# 4-20.net
KiCad netlist of a schematic drawn in Altium Designer
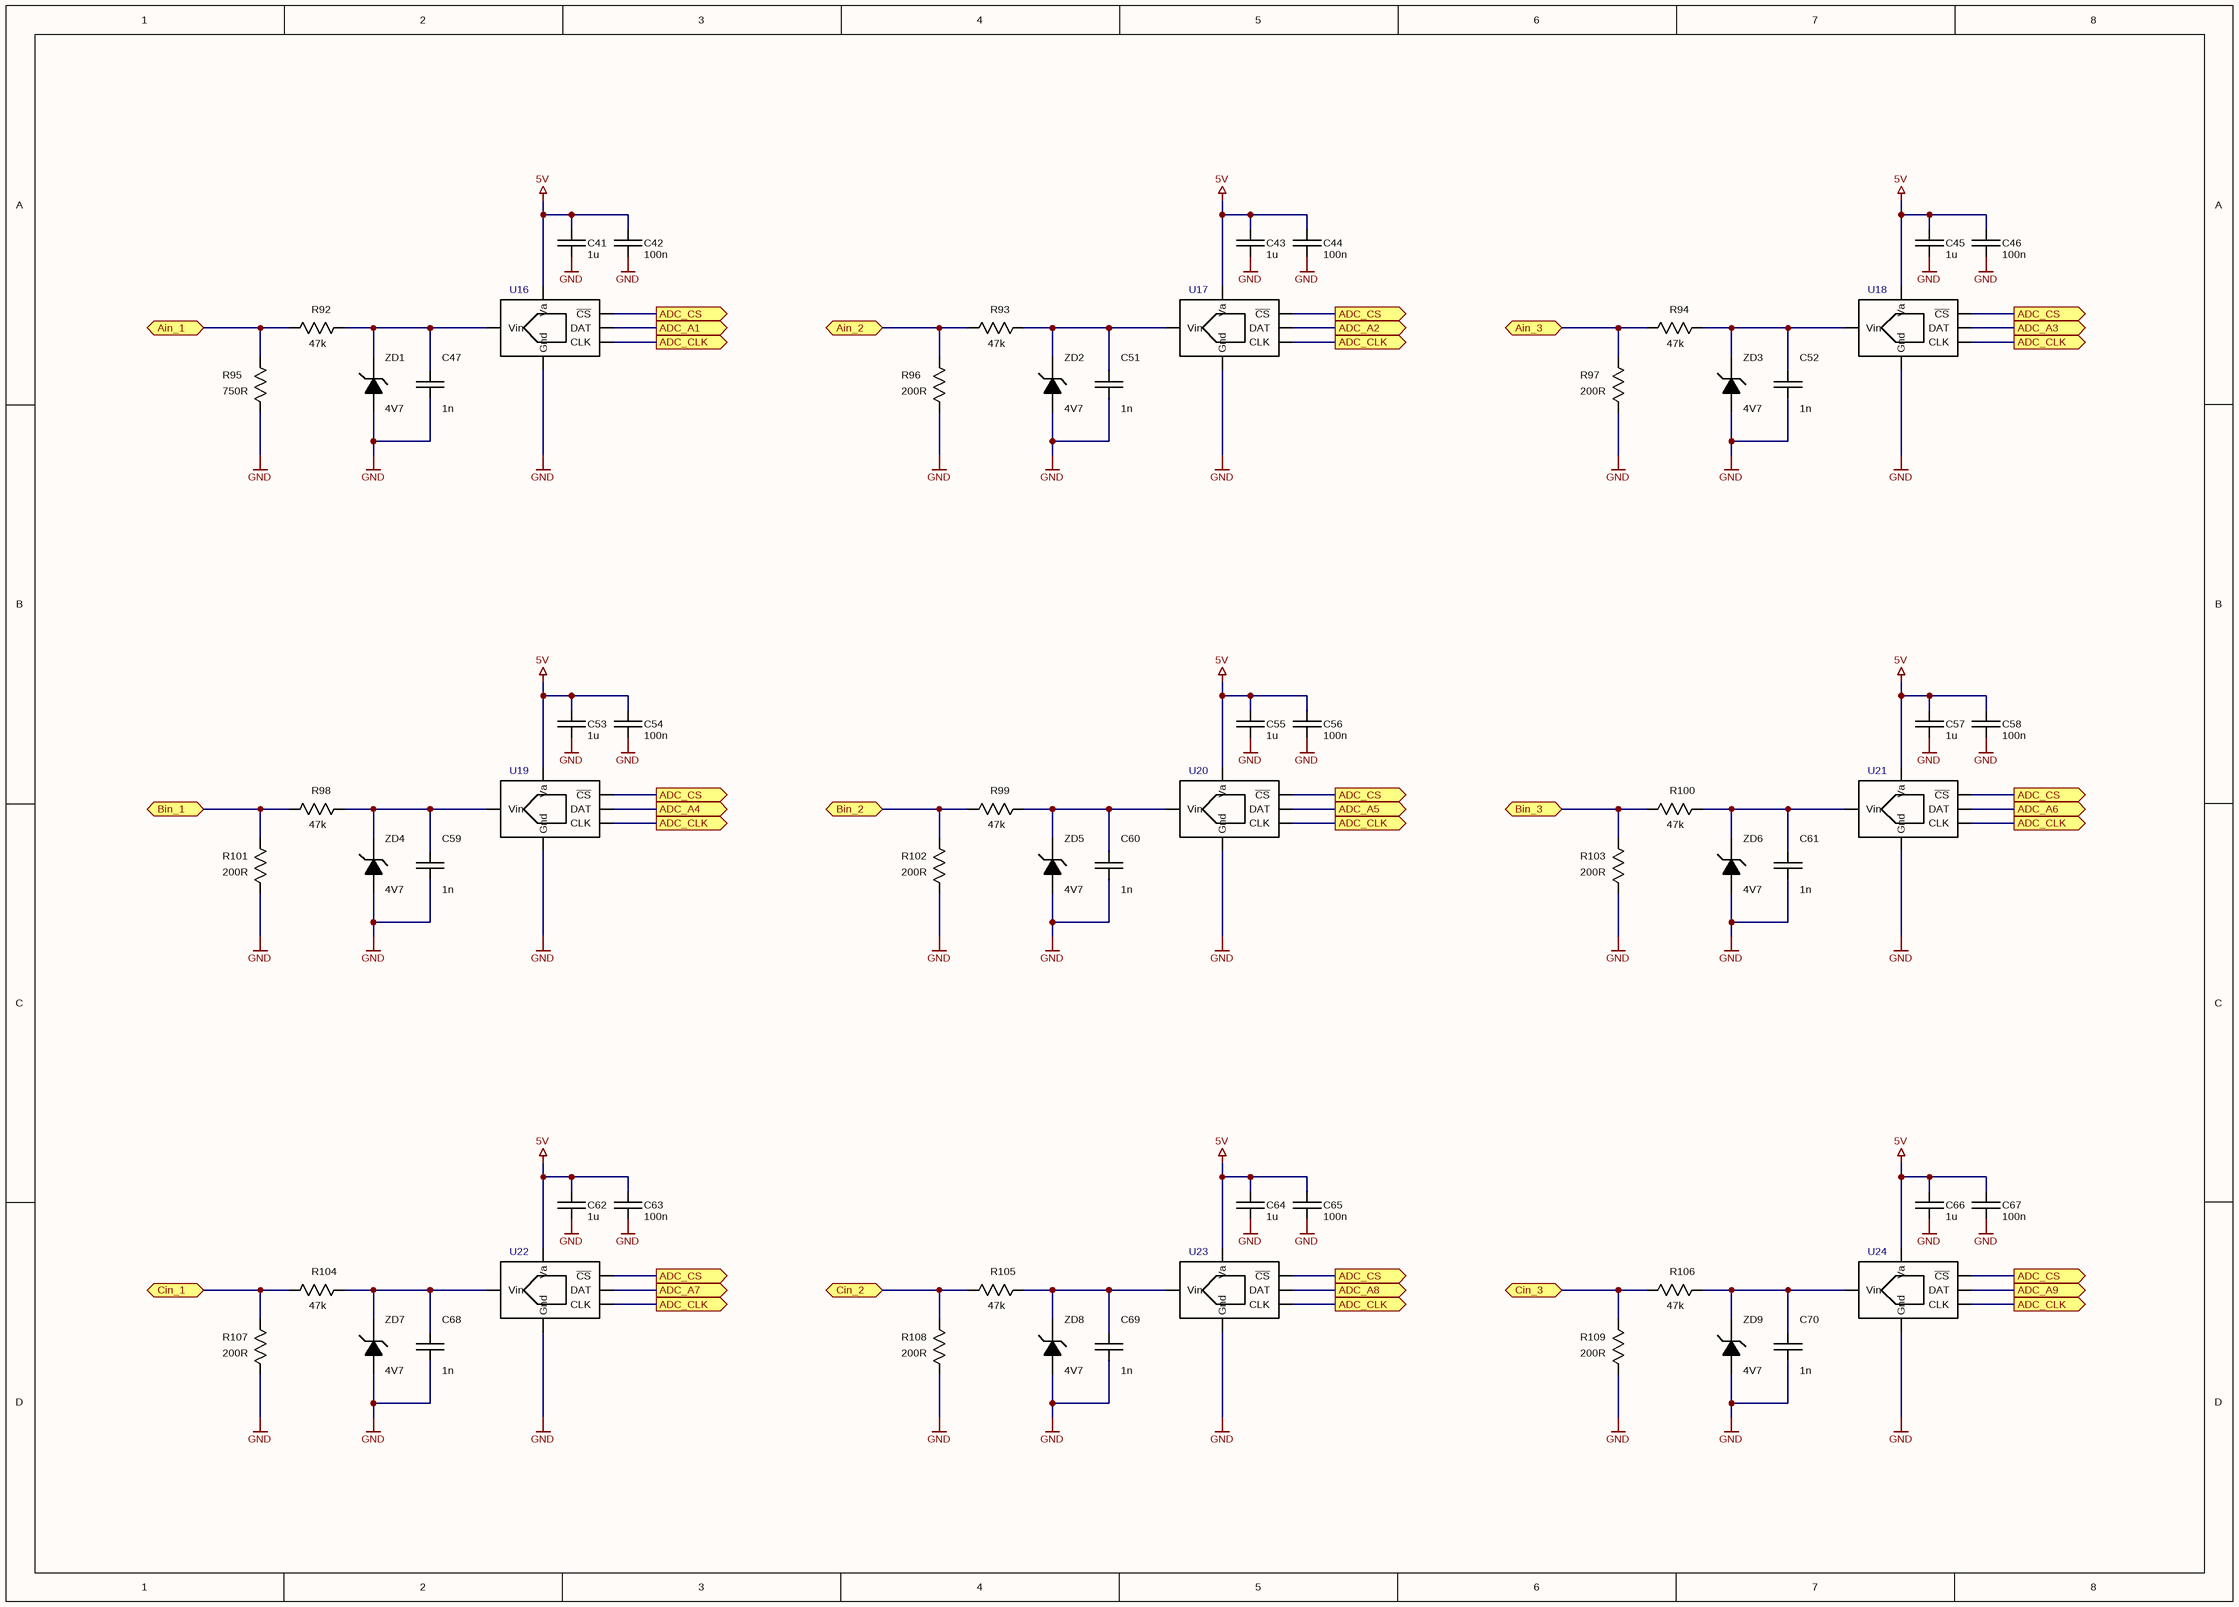
[diagram p0: 4-20.SchDoc]

(export (version "E")
  (design (tool "Eeschema 10.0.6"))
  (components
    (comp (ref "C41")
      (value "1u")
      (footprint "CAP CER 0603 NP")
      (description "CC0603KRX5R7BB105")
      (libsource (lib "levin") (part "Capacitor"))
    )
    (comp (ref "C42")
      (value "100n")
      (footprint "CAP CER 0603 NP")
      (description "CC0603KRX7R9BB104")
      (libsource (lib "levin") (part "Capacitor"))
    )
    (comp (ref "C43")
      (value "1u")
      (footprint "CAP CER 0603 NP")
      (description "CC0603KRX5R7BB105")
      (libsource (lib "levin") (part "Capacitor"))
    )
    (comp (ref "C44")
      (value "100n")
      (footprint "CAP CER 0603 NP")
      (description "CC0603KRX7R9BB104")
      (libsource (lib "levin") (part "Capacitor"))
    )
    (comp (ref "C45")
      (value "1u")
      (footprint "CAP CER 0603 NP")
      (description "CC0603KRX5R7BB105")
      (libsource (lib "levin") (part "Capacitor"))
    )
    (comp (ref "C46")
      (value "100n")
      (footprint "CAP CER 0603 NP")
      (description "CC0603KRX7R9BB104")
      (libsource (lib "levin") (part "Capacitor"))
    )
    (comp (ref "C47")
      (value "1n")
      (footprint "CAP CER 0603 NP")
      (description "CC0603KRX7R0BB102")
      (libsource (lib "levin") (part "Capacitor"))
    )
    (comp (ref "C51")
      (value "1n")
      (footprint "CAP CER 0603 NP")
      (description "CC0603KRX7R0BB102")
      (libsource (lib "levin") (part "Capacitor"))
    )
    (comp (ref "C52")
      (value "1n")
      (footprint "CAP CER 0603 NP")
      (description "CC0603KRX7R0BB102")
      (libsource (lib "levin") (part "Capacitor"))
    )
    (comp (ref "C53")
      (value "1u")
      (footprint "CAP CER 0603 NP")
      (description "CC0603KRX5R7BB105")
      (libsource (lib "levin") (part "Capacitor"))
    )
    (comp (ref "C54")
      (value "100n")
      (footprint "CAP CER 0603 NP")
      (description "CC0603KRX7R9BB104")
      (libsource (lib "levin") (part "Capacitor"))
    )
    (comp (ref "C55")
      (value "1u")
      (footprint "CAP CER 0603 NP")
      (description "CC0603KRX5R7BB105")
      (libsource (lib "levin") (part "Capacitor"))
    )
    (comp (ref "C56")
      (value "100n")
      (footprint "CAP CER 0603 NP")
      (description "CC0603KRX7R9BB104")
      (libsource (lib "levin") (part "Capacitor"))
    )
    (comp (ref "C57")
      (value "1u")
      (footprint "CAP CER 0603 NP")
      (description "CC0603KRX5R7BB105")
      (libsource (lib "levin") (part "Capacitor"))
    )
    (comp (ref "C58")
      (value "100n")
      (footprint "CAP CER 0603 NP")
      (description "CC0603KRX7R9BB104")
      (libsource (lib "levin") (part "Capacitor"))
    )
    (comp (ref "C59")
      (value "1n")
      (footprint "CAP CER 0603 NP")
      (description "CC0603KRX7R0BB102")
      (libsource (lib "levin") (part "Capacitor"))
    )
    (comp (ref "C60")
      (value "1n")
      (footprint "CAP CER 0603 NP")
      (description "CC0603KRX7R0BB102")
      (libsource (lib "levin") (part "Capacitor"))
    )
    (comp (ref "C61")
      (value "1n")
      (footprint "CAP CER 0603 NP")
      (description "CC0603KRX7R0BB102")
      (libsource (lib "levin") (part "Capacitor"))
    )
    (comp (ref "C62")
      (value "1u")
      (footprint "CAP CER 0603 NP")
      (description "CC0603KRX5R7BB105")
      (libsource (lib "levin") (part "Capacitor"))
    )
    (comp (ref "C63")
      (value "100n")
      (footprint "CAP CER 0603 NP")
      (description "CC0603KRX7R9BB104")
      (libsource (lib "levin") (part "Capacitor"))
    )
    (comp (ref "C64")
      (value "1u")
      (footprint "CAP CER 0603 NP")
      (description "CC0603KRX5R7BB105")
      (libsource (lib "levin") (part "Capacitor"))
    )
    (comp (ref "C65")
      (value "100n")
      (footprint "CAP CER 0603 NP")
      (description "CC0603KRX7R9BB104")
      (libsource (lib "levin") (part "Capacitor"))
    )
    (comp (ref "C66")
      (value "1u")
      (footprint "CAP CER 0603 NP")
      (description "CC0603KRX5R7BB105")
      (libsource (lib "levin") (part "Capacitor"))
    )
    (comp (ref "C67")
      (value "100n")
      (footprint "CAP CER 0603 NP")
      (description "CC0603KRX7R9BB104")
      (libsource (lib "levin") (part "Capacitor"))
    )
    (comp (ref "C68")
      (value "1n")
      (footprint "CAP CER 0603 NP")
      (description "CC0603KRX7R0BB102")
      (libsource (lib "levin") (part "Capacitor"))
    )
    (comp (ref "C69")
      (value "1n")
      (footprint "CAP CER 0603 NP")
      (description "CC0603KRX7R0BB102")
      (libsource (lib "levin") (part "Capacitor"))
    )
    (comp (ref "C70")
      (value "1n")
      (footprint "CAP CER 0603 NP")
      (description "CC0603KRX7R0BB102")
      (libsource (lib "levin") (part "Capacitor"))
    )
    (comp (ref "R92")
      (value "47k")
      (footprint "RES 0603")
      (description "RC0603FR-0747KL")
      (libsource (lib "levin") (part "Resistor"))
    )
    (comp (ref "R93")
      (value "47k")
      (footprint "RES 0603")
      (description "RC0603FR-0747KL")
      (libsource (lib "levin") (part "Resistor"))
    )
    (comp (ref "R94")
      (value "47k")
      (footprint "RES 0603")
      (description "RC0603FR-0747KL")
      (libsource (lib "levin") (part "Resistor"))
    )
    (comp (ref "R95")
      (value "750R")
      (footprint "levin:RES 1210")
      (description "RC1206FR-07750RL")
      (libsource (lib "levin") (part "Resistor"))
    )
    (comp (ref "R96")
      (value "200R")
      (footprint "levin:RES 1210")
      (description "RC1210FR-07200RL")
      (libsource (lib "levin") (part "Resistor"))
    )
    (comp (ref "R97")
      (value "200R")
      (footprint "levin:RES 1210")
      (description "RC1210FR-07200RL")
      (libsource (lib "levin") (part "Resistor"))
    )
    (comp (ref "R98")
      (value "47k")
      (footprint "RES 0603")
      (description "RC0603FR-0747KL")
      (libsource (lib "levin") (part "Resistor"))
    )
    (comp (ref "R99")
      (value "47k")
      (footprint "RES 0603")
      (description "RC0603FR-0747KL")
      (libsource (lib "levin") (part "Resistor"))
    )
    (comp (ref "R100")
      (value "47k")
      (footprint "RES 0603")
      (description "RC0603FR-0747KL")
      (libsource (lib "levin") (part "Resistor"))
    )
    (comp (ref "R101")
      (value "200R")
      (footprint "levin:RES 1210")
      (description "RC1210FR-07200RL")
      (libsource (lib "levin") (part "Resistor"))
    )
    (comp (ref "R102")
      (value "200R")
      (footprint "levin:RES 1210")
      (description "RC1210FR-07200RL")
      (libsource (lib "levin") (part "Resistor"))
    )
    (comp (ref "R103")
      (value "200R")
      (footprint "levin:RES 1210")
      (description "RC1210FR-07200RL")
      (libsource (lib "levin") (part "Resistor"))
    )
    (comp (ref "R104")
      (value "47k")
      (footprint "RES 0603")
      (description "RC0603FR-0747KL")
      (libsource (lib "levin") (part "Resistor"))
    )
    (comp (ref "R105")
      (value "47k")
      (footprint "RES 0603")
      (description "RC0603FR-0747KL")
      (libsource (lib "levin") (part "Resistor"))
    )
    (comp (ref "R106")
      (value "47k")
      (footprint "RES 0603")
      (description "RC0603FR-0747KL")
      (libsource (lib "levin") (part "Resistor"))
    )
    (comp (ref "R107")
      (value "200R")
      (footprint "levin:RES 1210")
      (description "RC1210FR-07200RL")
      (libsource (lib "levin") (part "Resistor"))
    )
    (comp (ref "R108")
      (value "200R")
      (footprint "levin:RES 1210")
      (description "RC1210FR-07200RL")
      (libsource (lib "levin") (part "Resistor"))
    )
    (comp (ref "R109")
      (value "200R")
      (footprint "levin:RES 1210")
      (description "RC1210FR-07200RL")
      (libsource (lib "levin") (part "Resistor"))
    )
    (comp (ref "U16")
      (value "SAR ADC")
      (footprint "SOT-23-6")
      (description "ADC121S021CIMF")
      (libsource (lib "levin") (part "ADC121"))
    )
    (comp (ref "U17")
      (value "SAR ADC")
      (footprint "SOT-23-6")
      (description "ADC121S021CIMF")
      (libsource (lib "levin") (part "ADC121"))
    )
    (comp (ref "U18")
      (value "SAR ADC")
      (footprint "SOT-23-6")
      (description "ADC121S021CIMF")
      (libsource (lib "levin") (part "ADC121"))
    )
    (comp (ref "U19")
      (value "SAR ADC")
      (footprint "SOT-23-6")
      (description "ADC121S021CIMF")
      (libsource (lib "levin") (part "ADC121"))
    )
    (comp (ref "U20")
      (value "SAR ADC")
      (footprint "SOT-23-6")
      (description "ADC121S021CIMF")
      (libsource (lib "levin") (part "ADC121"))
    )
    (comp (ref "U21")
      (value "SAR ADC")
      (footprint "SOT-23-6")
      (description "ADC121S021CIMF")
      (libsource (lib "levin") (part "ADC121"))
    )
    (comp (ref "U22")
      (value "SAR ADC")
      (footprint "SOT-23-6")
      (description "ADC121S021CIMF")
      (libsource (lib "levin") (part "ADC121"))
    )
    (comp (ref "U23")
      (value "SAR ADC")
      (footprint "SOT-23-6")
      (description "ADC121S021CIMF")
      (libsource (lib "levin") (part "ADC121"))
    )
    (comp (ref "U24")
      (value "SAR ADC")
      (footprint "SOT-23-6")
      (description "ADC121S021CIMF")
      (libsource (lib "levin") (part "ADC121"))
    )
    (comp (ref "ZD1")
      (value "4V7")
      (footprint "SOD323 (SC-76) - Reflow")
      (description "BZX384-C4V7")
      (libsource (lib "levin") (part "Diode Zenner"))
    )
    (comp (ref "ZD2")
      (value "4V7")
      (footprint "SOD323 (SC-76) - Reflow")
      (description "BZX384-C4V7")
      (libsource (lib "levin") (part "Diode Zenner"))
    )
    (comp (ref "ZD3")
      (value "4V7")
      (footprint "SOD323 (SC-76) - Reflow")
      (description "BZX384-C4V7")
      (libsource (lib "levin") (part "Diode Zenner"))
    )
    (comp (ref "ZD4")
      (value "4V7")
      (footprint "SOD323 (SC-76) - Reflow")
      (description "BZX384-C4V7")
      (libsource (lib "levin") (part "Diode Zenner"))
    )
    (comp (ref "ZD5")
      (value "4V7")
      (footprint "SOD323 (SC-76) - Reflow")
      (description "BZX384-C4V7")
      (libsource (lib "levin") (part "Diode Zenner"))
    )
    (comp (ref "ZD6")
      (value "4V7")
      (footprint "SOD323 (SC-76) - Reflow")
      (description "BZX384-C4V7")
      (libsource (lib "levin") (part "Diode Zenner"))
    )
    (comp (ref "ZD7")
      (value "4V7")
      (footprint "SOD323 (SC-76) - Reflow")
      (description "BZX384-C4V7")
      (libsource (lib "levin") (part "Diode Zenner"))
    )
    (comp (ref "ZD8")
      (value "4V7")
      (footprint "SOD323 (SC-76) - Reflow")
      (description "BZX384-C4V7")
      (libsource (lib "levin") (part "Diode Zenner"))
    )
    (comp (ref "ZD9")
      (value "4V7")
      (footprint "SOD323 (SC-76) - Reflow")
      (description "BZX384-C4V7")
      (libsource (lib "levin") (part "Diode Zenner"))
    )
  )
  (nets
    (net (code "1") (name "/ADC_A1") (class "Default")
      (node (ref "U16") (pin "5") (pinfunction "DAT_5") (pintype "passive"))
    )
    (net (code "2") (name "/ADC_A2") (class "Default")
      (node (ref "U17") (pin "5") (pinfunction "DAT_5") (pintype "passive"))
    )
    (net (code "3") (name "/ADC_A3") (class "Default")
      (node (ref "U18") (pin "5") (pinfunction "DAT_5") (pintype "passive"))
    )
    (net (code "4") (name "/ADC_A4") (class "Default")
      (node (ref "U19") (pin "5") (pinfunction "DAT_5") (pintype "passive"))
    )
    (net (code "5") (name "/ADC_A5") (class "Default")
      (node (ref "U20") (pin "5") (pinfunction "DAT_5") (pintype "passive"))
    )
    (net (code "6") (name "/ADC_A6") (class "Default")
      (node (ref "U21") (pin "5") (pinfunction "DAT_5") (pintype "passive"))
    )
    (net (code "7") (name "/ADC_A7") (class "Default")
      (node (ref "U22") (pin "5") (pinfunction "DAT_5") (pintype "passive"))
    )
    (net (code "8") (name "/ADC_A8") (class "Default")
      (node (ref "U23") (pin "5") (pinfunction "DAT_5") (pintype "passive"))
    )
    (net (code "9") (name "/ADC_A9") (class "Default")
      (node (ref "U24") (pin "5") (pinfunction "DAT_5") (pintype "passive"))
    )
    (net (code "10") (name "/ADC_CLK") (class "Default")
      (node (ref "U16") (pin "4") (pinfunction "CLK_4") (pintype "passive"))
      (node (ref "U17") (pin "4") (pinfunction "CLK_4") (pintype "passive"))
      (node (ref "U18") (pin "4") (pinfunction "CLK_4") (pintype "passive"))
      (node (ref "U19") (pin "4") (pinfunction "CLK_4") (pintype "passive"))
      (node (ref "U20") (pin "4") (pinfunction "CLK_4") (pintype "passive"))
      (node (ref "U21") (pin "4") (pinfunction "CLK_4") (pintype "passive"))
      (node (ref "U22") (pin "4") (pinfunction "CLK_4") (pintype "passive"))
      (node (ref "U23") (pin "4") (pinfunction "CLK_4") (pintype "passive"))
      (node (ref "U24") (pin "4") (pinfunction "CLK_4") (pintype "passive"))
    )
    (net (code "11") (name "/ADC_CS") (class "Default")
      (node (ref "U16") (pin "6") (pinfunction "~{CS}_6") (pintype "passive"))
      (node (ref "U17") (pin "6") (pinfunction "~{CS}_6") (pintype "passive"))
      (node (ref "U18") (pin "6") (pinfunction "~{CS}_6") (pintype "passive"))
      (node (ref "U19") (pin "6") (pinfunction "~{CS}_6") (pintype "passive"))
      (node (ref "U20") (pin "6") (pinfunction "~{CS}_6") (pintype "passive"))
      (node (ref "U21") (pin "6") (pinfunction "~{CS}_6") (pintype "passive"))
      (node (ref "U22") (pin "6") (pinfunction "~{CS}_6") (pintype "passive"))
      (node (ref "U23") (pin "6") (pinfunction "~{CS}_6") (pintype "passive"))
      (node (ref "U24") (pin "6") (pinfunction "~{CS}_6") (pintype "passive"))
    )
    (net (code "12") (name "/Ain_1") (class "Default")
      (node (ref "R92") (pin "2") (pinfunction "2_2") (pintype "passive"))
      (node (ref "R95") (pin "2") (pinfunction "2_2") (pintype "passive"))
    )
    (net (code "13") (name "/Ain_2") (class "Default")
      (node (ref "R93") (pin "2") (pinfunction "2_2") (pintype "passive"))
      (node (ref "R96") (pin "2") (pinfunction "2_2") (pintype "passive"))
    )
    (net (code "14") (name "/Ain_3") (class "Default")
      (node (ref "R94") (pin "2") (pinfunction "2_2") (pintype "passive"))
      (node (ref "R97") (pin "2") (pinfunction "2_2") (pintype "passive"))
    )
    (net (code "15") (name "/Bin_1") (class "Default")
      (node (ref "R101") (pin "2") (pinfunction "2_2") (pintype "passive"))
      (node (ref "R98") (pin "2") (pinfunction "2_2") (pintype "passive"))
    )
    (net (code "16") (name "/Bin_2") (class "Default")
      (node (ref "R102") (pin "2") (pinfunction "2_2") (pintype "passive"))
      (node (ref "R99") (pin "2") (pinfunction "2_2") (pintype "passive"))
    )
    (net (code "17") (name "/Bin_3") (class "Default")
      (node (ref "R100") (pin "2") (pinfunction "2_2") (pintype "passive"))
      (node (ref "R103") (pin "2") (pinfunction "2_2") (pintype "passive"))
    )
    (net (code "18") (name "/Cin_1") (class "Default")
      (node (ref "R104") (pin "2") (pinfunction "2_2") (pintype "passive"))
      (node (ref "R107") (pin "2") (pinfunction "2_2") (pintype "passive"))
    )
    (net (code "19") (name "/Cin_2") (class "Default")
      (node (ref "R105") (pin "2") (pinfunction "2_2") (pintype "passive"))
      (node (ref "R108") (pin "2") (pinfunction "2_2") (pintype "passive"))
    )
    (net (code "20") (name "/Cin_3") (class "Default")
      (node (ref "R106") (pin "2") (pinfunction "2_2") (pintype "passive"))
      (node (ref "R109") (pin "2") (pinfunction "2_2") (pintype "passive"))
    )
    (net (code "21") (name "5V") (class "Default")
      (node (ref "C41") (pin "1") (pinfunction "1_1") (pintype "passive"))
      (node (ref "C42") (pin "2") (pinfunction "2_2") (pintype "passive"))
      (node (ref "C43") (pin "1") (pinfunction "1_1") (pintype "passive"))
      (node (ref "C44") (pin "2") (pinfunction "2_2") (pintype "passive"))
      (node (ref "C45") (pin "1") (pinfunction "1_1") (pintype "passive"))
      (node (ref "C46") (pin "2") (pinfunction "2_2") (pintype "passive"))
      (node (ref "C53") (pin "1") (pinfunction "1_1") (pintype "passive"))
      (node (ref "C54") (pin "2") (pinfunction "2_2") (pintype "passive"))
      (node (ref "C55") (pin "1") (pinfunction "1_1") (pintype "passive"))
      (node (ref "C56") (pin "2") (pinfunction "2_2") (pintype "passive"))
      (node (ref "C57") (pin "1") (pinfunction "1_1") (pintype "passive"))
      (node (ref "C58") (pin "2") (pinfunction "2_2") (pintype "passive"))
      (node (ref "C62") (pin "1") (pinfunction "1_1") (pintype "passive"))
      (node (ref "C63") (pin "2") (pinfunction "2_2") (pintype "passive"))
      (node (ref "C64") (pin "1") (pinfunction "1_1") (pintype "passive"))
      (node (ref "C65") (pin "2") (pinfunction "2_2") (pintype "passive"))
      (node (ref "C66") (pin "1") (pinfunction "1_1") (pintype "passive"))
      (node (ref "C67") (pin "2") (pinfunction "2_2") (pintype "passive"))
      (node (ref "U16") (pin "1") (pinfunction "Va_1") (pintype "passive"))
      (node (ref "U17") (pin "1") (pinfunction "Va_1") (pintype "passive"))
      (node (ref "U18") (pin "1") (pinfunction "Va_1") (pintype "passive"))
      (node (ref "U19") (pin "1") (pinfunction "Va_1") (pintype "passive"))
      (node (ref "U20") (pin "1") (pinfunction "Va_1") (pintype "passive"))
      (node (ref "U21") (pin "1") (pinfunction "Va_1") (pintype "passive"))
      (node (ref "U22") (pin "1") (pinfunction "Va_1") (pintype "passive"))
      (node (ref "U23") (pin "1") (pinfunction "Va_1") (pintype "passive"))
      (node (ref "U24") (pin "1") (pinfunction "Va_1") (pintype "passive"))
    )
    (net (code "22") (name "GND") (class "Default")
      (node (ref "C41") (pin "2") (pinfunction "2_2") (pintype "passive"))
      (node (ref "C42") (pin "1") (pinfunction "1_1") (pintype "passive"))
      (node (ref "C43") (pin "2") (pinfunction "2_2") (pintype "passive"))
      (node (ref "C44") (pin "1") (pinfunction "1_1") (pintype "passive"))
      (node (ref "C45") (pin "2") (pinfunction "2_2") (pintype "passive"))
      (node (ref "C46") (pin "1") (pinfunction "1_1") (pintype "passive"))
      (node (ref "C47") (pin "1") (pinfunction "1_1") (pintype "passive"))
      (node (ref "C51") (pin "1") (pinfunction "1_1") (pintype "passive"))
      (node (ref "C52") (pin "1") (pinfunction "1_1") (pintype "passive"))
      (node (ref "C53") (pin "2") (pinfunction "2_2") (pintype "passive"))
      (node (ref "C54") (pin "1") (pinfunction "1_1") (pintype "passive"))
      (node (ref "C55") (pin "2") (pinfunction "2_2") (pintype "passive"))
      (node (ref "C56") (pin "1") (pinfunction "1_1") (pintype "passive"))
      (node (ref "C57") (pin "2") (pinfunction "2_2") (pintype "passive"))
      (node (ref "C58") (pin "1") (pinfunction "1_1") (pintype "passive"))
      (node (ref "C59") (pin "1") (pinfunction "1_1") (pintype "passive"))
      (node (ref "C60") (pin "1") (pinfunction "1_1") (pintype "passive"))
      (node (ref "C61") (pin "1") (pinfunction "1_1") (pintype "passive"))
      (node (ref "C62") (pin "2") (pinfunction "2_2") (pintype "passive"))
      (node (ref "C63") (pin "1") (pinfunction "1_1") (pintype "passive"))
      (node (ref "C64") (pin "2") (pinfunction "2_2") (pintype "passive"))
      (node (ref "C65") (pin "1") (pinfunction "1_1") (pintype "passive"))
      (node (ref "C66") (pin "2") (pinfunction "2_2") (pintype "passive"))
      (node (ref "C67") (pin "1") (pinfunction "1_1") (pintype "passive"))
      (node (ref "C68") (pin "1") (pinfunction "1_1") (pintype "passive"))
      (node (ref "C69") (pin "1") (pinfunction "1_1") (pintype "passive"))
      (node (ref "C70") (pin "1") (pinfunction "1_1") (pintype "passive"))
      (node (ref "R101") (pin "1") (pinfunction "1_1") (pintype "passive"))
      (node (ref "R102") (pin "1") (pinfunction "1_1") (pintype "passive"))
      (node (ref "R103") (pin "1") (pinfunction "1_1") (pintype "passive"))
      (node (ref "R107") (pin "1") (pinfunction "1_1") (pintype "passive"))
      (node (ref "R108") (pin "1") (pinfunction "1_1") (pintype "passive"))
      (node (ref "R109") (pin "1") (pinfunction "1_1") (pintype "passive"))
      (node (ref "R95") (pin "1") (pinfunction "1_1") (pintype "passive"))
      (node (ref "R96") (pin "1") (pinfunction "1_1") (pintype "passive"))
      (node (ref "R97") (pin "1") (pinfunction "1_1") (pintype "passive"))
      (node (ref "U16") (pin "2") (pinfunction "Gnd_2") (pintype "passive"))
      (node (ref "U17") (pin "2") (pinfunction "Gnd_2") (pintype "passive"))
      (node (ref "U18") (pin "2") (pinfunction "Gnd_2") (pintype "passive"))
      (node (ref "U19") (pin "2") (pinfunction "Gnd_2") (pintype "passive"))
      (node (ref "U20") (pin "2") (pinfunction "Gnd_2") (pintype "passive"))
      (node (ref "U21") (pin "2") (pinfunction "Gnd_2") (pintype "passive"))
      (node (ref "U22") (pin "2") (pinfunction "Gnd_2") (pintype "passive"))
      (node (ref "U23") (pin "2") (pinfunction "Gnd_2") (pintype "passive"))
      (node (ref "U24") (pin "2") (pinfunction "Gnd_2") (pintype "passive"))
      (node (ref "ZD1") (pin "1") (pinfunction "A_1") (pintype "passive"))
      (node (ref "ZD2") (pin "1") (pinfunction "A_1") (pintype "passive"))
      (node (ref "ZD3") (pin "1") (pinfunction "A_1") (pintype "passive"))
      (node (ref "ZD4") (pin "1") (pinfunction "A_1") (pintype "passive"))
      (node (ref "ZD5") (pin "1") (pinfunction "A_1") (pintype "passive"))
      (node (ref "ZD6") (pin "1") (pinfunction "A_1") (pintype "passive"))
      (node (ref "ZD7") (pin "1") (pinfunction "A_1") (pintype "passive"))
      (node (ref "ZD8") (pin "1") (pinfunction "A_1") (pintype "passive"))
      (node (ref "ZD9") (pin "1") (pinfunction "A_1") (pintype "passive"))
    )
    (net (code "23") (name "Net-(U16-Vin)") (class "Default")
      (node (ref "C47") (pin "2") (pinfunction "2_2") (pintype "passive"))
      (node (ref "R92") (pin "1") (pinfunction "1_1") (pintype "passive"))
      (node (ref "U16") (pin "3") (pinfunction "Vin_3") (pintype "passive"))
      (node (ref "ZD1") (pin "2") (pinfunction "C_2") (pintype "passive"))
    )
    (net (code "24") (name "Net-(U17-Vin)") (class "Default")
      (node (ref "C51") (pin "2") (pinfunction "2_2") (pintype "passive"))
      (node (ref "R93") (pin "1") (pinfunction "1_1") (pintype "passive"))
      (node (ref "U17") (pin "3") (pinfunction "Vin_3") (pintype "passive"))
      (node (ref "ZD2") (pin "2") (pinfunction "C_2") (pintype "passive"))
    )
    (net (code "25") (name "Net-(U18-Vin)") (class "Default")
      (node (ref "C52") (pin "2") (pinfunction "2_2") (pintype "passive"))
      (node (ref "R94") (pin "1") (pinfunction "1_1") (pintype "passive"))
      (node (ref "U18") (pin "3") (pinfunction "Vin_3") (pintype "passive"))
      (node (ref "ZD3") (pin "2") (pinfunction "C_2") (pintype "passive"))
    )
    (net (code "26") (name "Net-(U19-Vin)") (class "Default")
      (node (ref "C59") (pin "2") (pinfunction "2_2") (pintype "passive"))
      (node (ref "R98") (pin "1") (pinfunction "1_1") (pintype "passive"))
      (node (ref "U19") (pin "3") (pinfunction "Vin_3") (pintype "passive"))
      (node (ref "ZD4") (pin "2") (pinfunction "C_2") (pintype "passive"))
    )
    (net (code "27") (name "Net-(U20-Vin)") (class "Default")
      (node (ref "C60") (pin "2") (pinfunction "2_2") (pintype "passive"))
      (node (ref "R99") (pin "1") (pinfunction "1_1") (pintype "passive"))
      (node (ref "U20") (pin "3") (pinfunction "Vin_3") (pintype "passive"))
      (node (ref "ZD5") (pin "2") (pinfunction "C_2") (pintype "passive"))
    )
    (net (code "28") (name "Net-(U21-Vin)") (class "Default")
      (node (ref "C61") (pin "2") (pinfunction "2_2") (pintype "passive"))
      (node (ref "R100") (pin "1") (pinfunction "1_1") (pintype "passive"))
      (node (ref "U21") (pin "3") (pinfunction "Vin_3") (pintype "passive"))
      (node (ref "ZD6") (pin "2") (pinfunction "C_2") (pintype "passive"))
    )
    (net (code "29") (name "Net-(U22-Vin)") (class "Default")
      (node (ref "C68") (pin "2") (pinfunction "2_2") (pintype "passive"))
      (node (ref "R104") (pin "1") (pinfunction "1_1") (pintype "passive"))
      (node (ref "U22") (pin "3") (pinfunction "Vin_3") (pintype "passive"))
      (node (ref "ZD7") (pin "2") (pinfunction "C_2") (pintype "passive"))
    )
    (net (code "30") (name "Net-(U23-Vin)") (class "Default")
      (node (ref "C69") (pin "2") (pinfunction "2_2") (pintype "passive"))
      (node (ref "R105") (pin "1") (pinfunction "1_1") (pintype "passive"))
      (node (ref "U23") (pin "3") (pinfunction "Vin_3") (pintype "passive"))
      (node (ref "ZD8") (pin "2") (pinfunction "C_2") (pintype "passive"))
    )
    (net (code "31") (name "Net-(U24-Vin)") (class "Default")
      (node (ref "C70") (pin "2") (pinfunction "2_2") (pintype "passive"))
      (node (ref "R106") (pin "1") (pinfunction "1_1") (pintype "passive"))
      (node (ref "U24") (pin "3") (pinfunction "Vin_3") (pintype "passive"))
      (node (ref "ZD9") (pin "2") (pinfunction "C_2") (pintype "passive"))
    )
  )
)
